# Modular_BO.net
KiCad netlist of a schematic drawn in Altium Designer
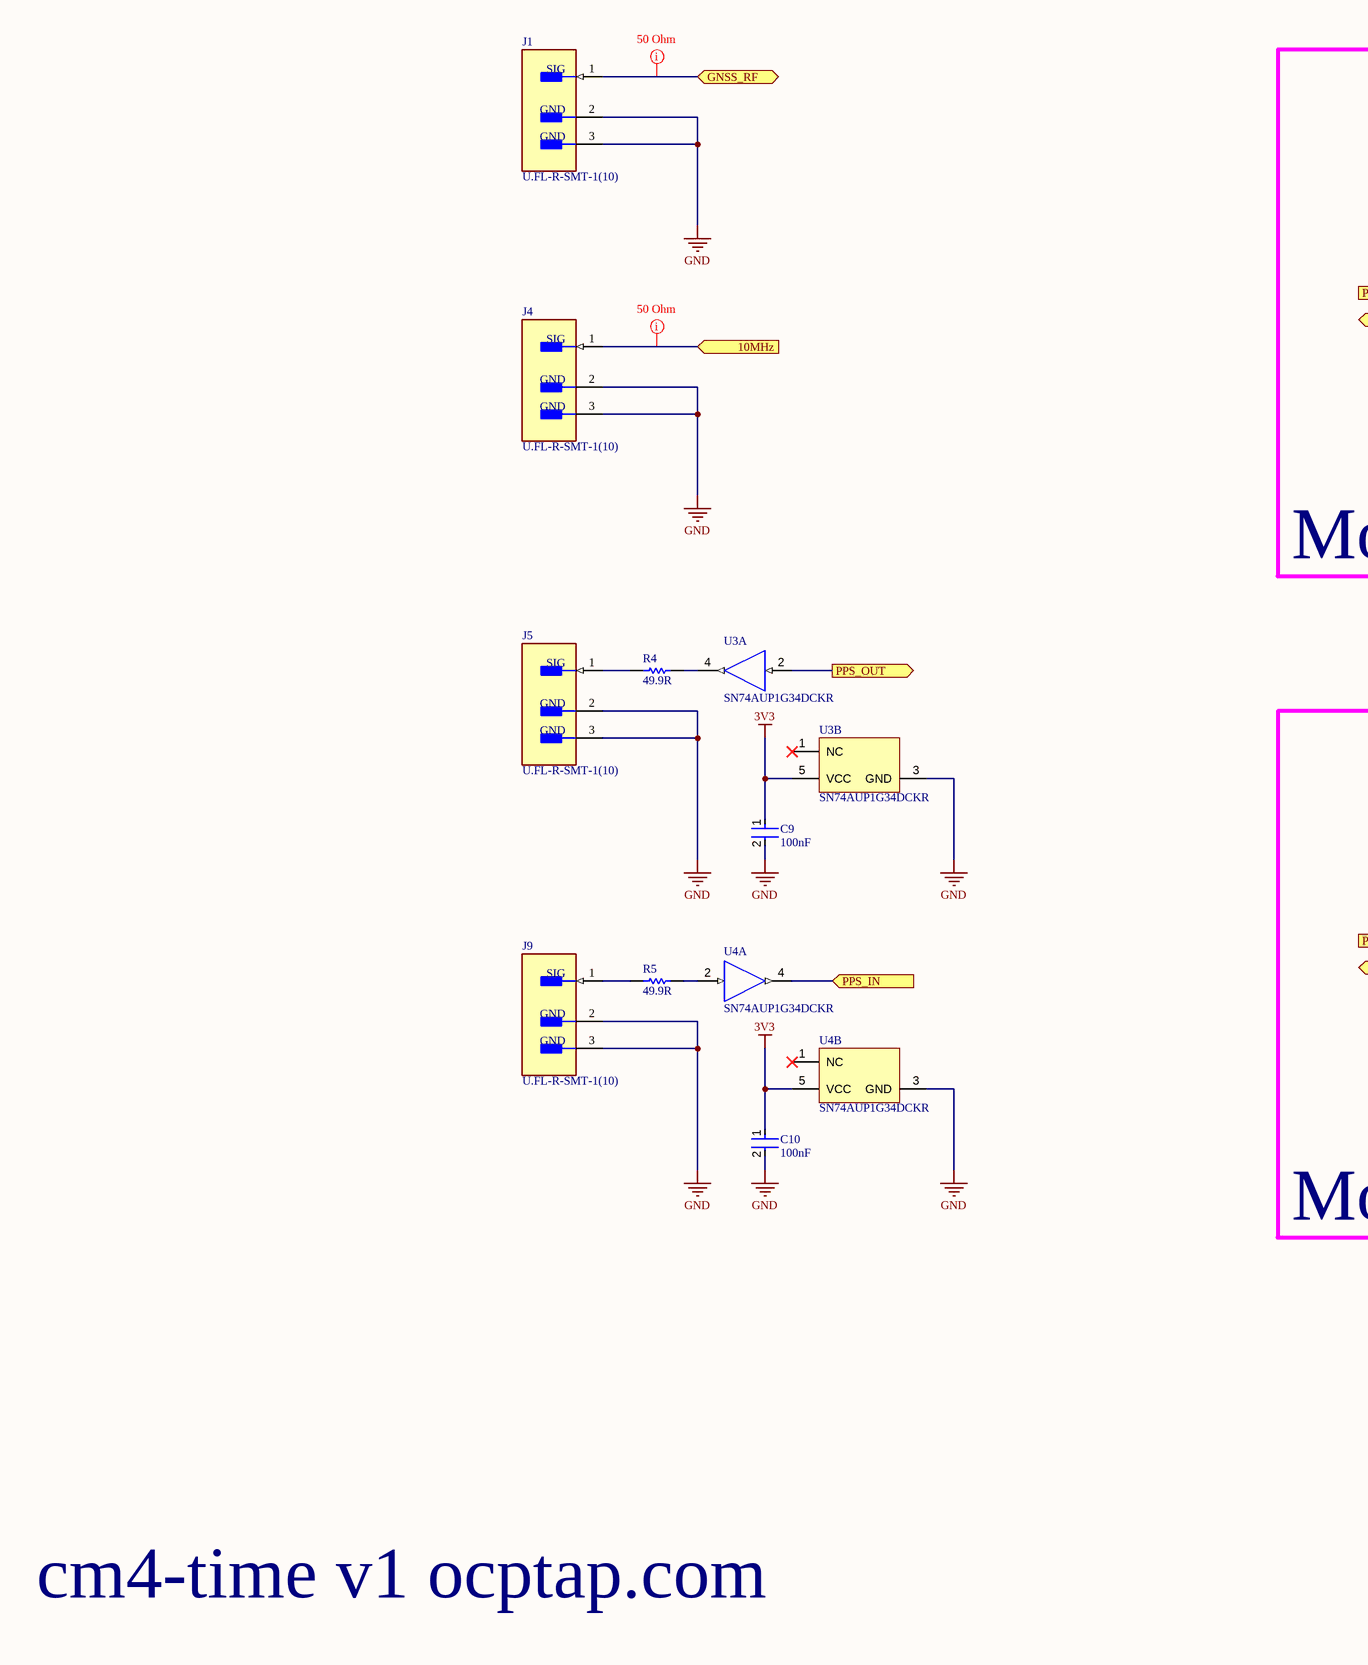
[diagram p0: Modular_BO.SchDoc, left]
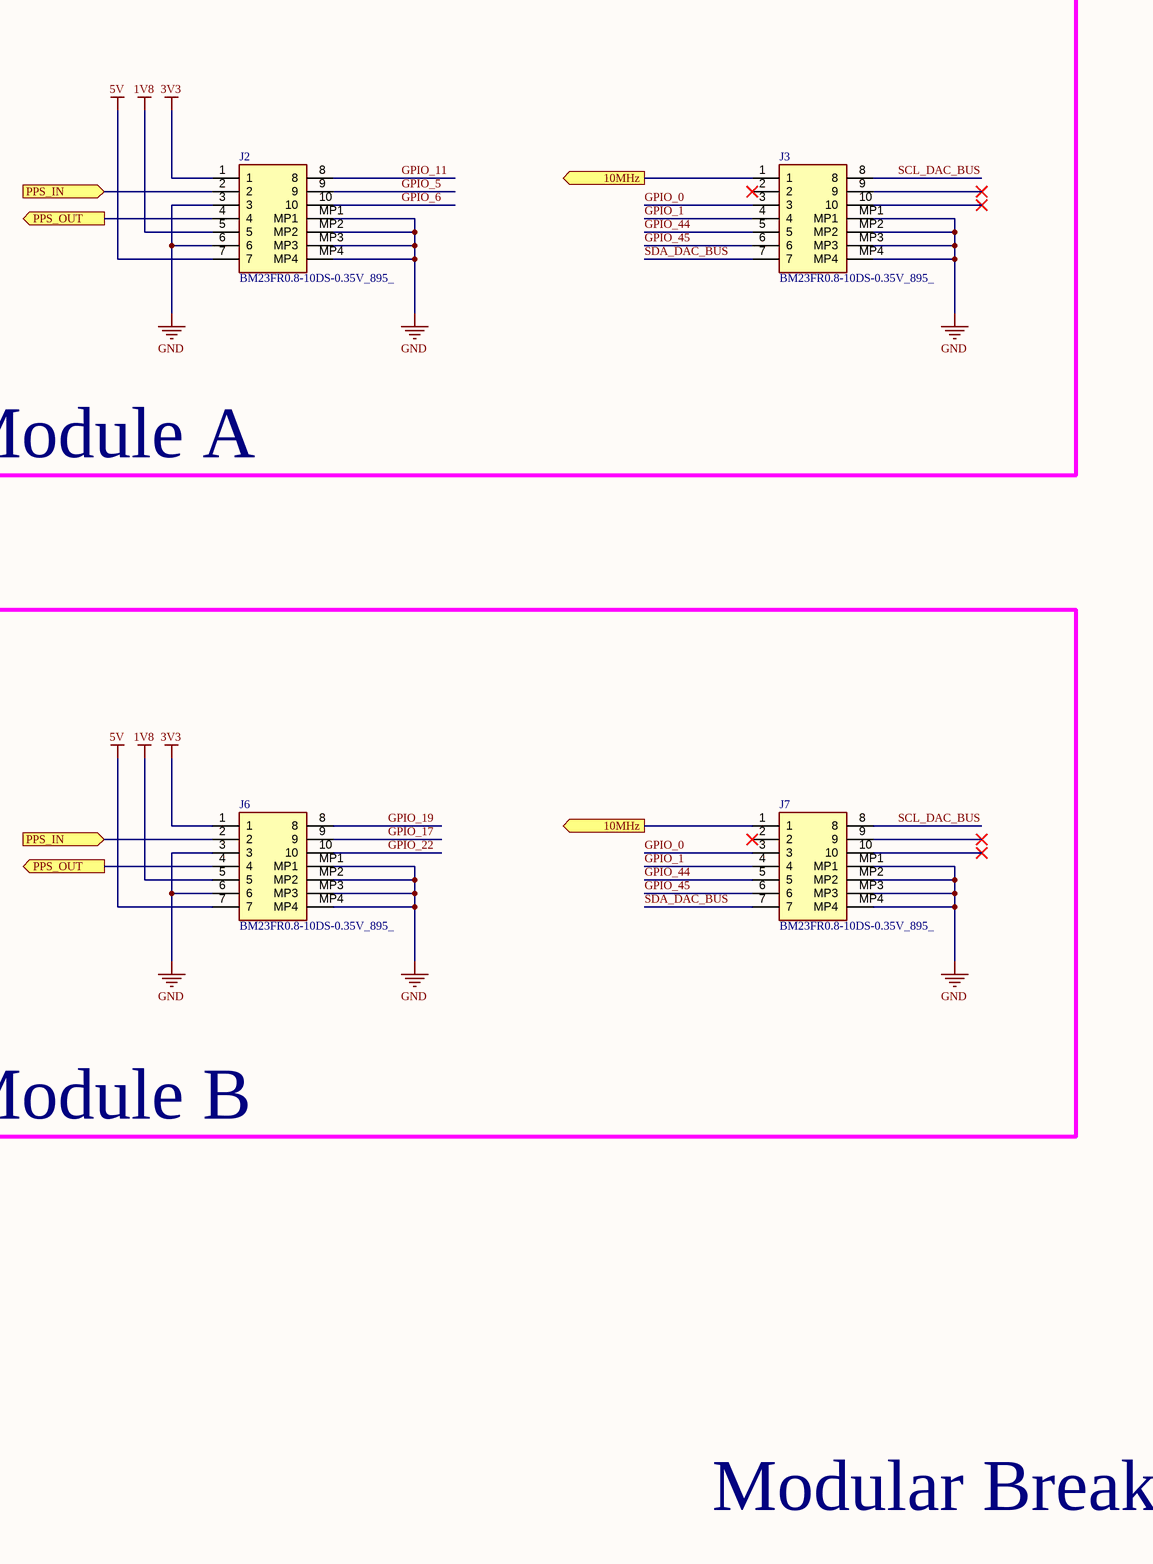
[diagram p1: Modular_BO.SchDoc, right]

(export (version "E")
  (design (tool "Eeschema 10.0.6"))
  (components
    (comp (ref "C9")
      (value "100nF")
      (footprint "FP-C0603C-CF-MFG")
      (description "CAP CER 0.1UF 50V 20% X7R 0603")
      (fields
        (field (name "MANUFACTURER PART NUMBER") "C0603C104M5RACTU")
        (field (name "MANUFACTURER") "KEMET")
      )
      (libsource (lib "Altium Content Vault") (part "b4654b650e69147ec39a6b967a45e02"))
    )
    (comp (ref "C10")
      (value "100nF")
      (footprint "FP-C0603C-CF-MFG")
      (description "CAP CER 0.1UF 50V 20% X7R 0603")
      (fields
        (field (name "MANUFACTURER PART NUMBER") "C0603C104M5RACTU")
        (field (name "MANUFACTURER") "KEMET")
      )
      (libsource (lib "Altium Content Vault") (part "b4654b650e69147ec39a6b967a45e02"))
    )
    (comp (ref "J1")
      (value "U.FL-R-SMT-1(10)")
      (footprint "FP-U_FL-R-SMT-1_10-MFG")
      (description "CONN U.FL RCPT STR 50 OHM SMD")
      (libsource (lib "Altium Content Vault") (part "7158abf7d987fa84906f6fb0d115710"))
    )
    (comp (ref "J2")
      (value "BM23FR0.8-10DS-0.35V_895_")
      (footprint "SamacSys:BM23FR0810DS035V895")
      (description "Connector")
      (fields
        (field (name "MANUFACTURER_PART_NUMBER") "BM23FR0.8-10DS-0.35V(895)")
        (field (name "MOUSER PART NUMBER") "798-3FR0810DS035V895")
      )
      (libsource (lib "*") (part "BM23FR0.8-10DS-0.35V_895_"))
    )
    (comp (ref "J3")
      (value "BM23FR0.8-10DS-0.35V_895_")
      (footprint "SamacSys:BM23FR0810DS035V895")
      (description "Connector")
      (fields
        (field (name "MANUFACTURER_PART_NUMBER") "BM23FR0.8-10DS-0.35V(895)")
        (field (name "MOUSER PART NUMBER") "798-3FR0810DS035V895")
      )
      (libsource (lib "*") (part "BM23FR0.8-10DS-0.35V_895_"))
    )
    (comp (ref "J4")
      (value "U.FL-R-SMT-1(10)")
      (footprint "FP-U_FL-R-SMT-1_10-MFG")
      (description "CONN U.FL RCPT STR 50 OHM SMD")
      (libsource (lib "Altium Content Vault") (part "7158abf7d987fa84906f6fb0d115710"))
    )
    (comp (ref "J5")
      (value "U.FL-R-SMT-1(10)")
      (footprint "FP-U_FL-R-SMT-1_10-MFG")
      (description "CONN U.FL RCPT STR 50 OHM SMD")
      (libsource (lib "Altium Content Vault") (part "7158abf7d987fa84906f6fb0d115710"))
    )
    (comp (ref "J6")
      (value "BM23FR0.8-10DS-0.35V_895_")
      (footprint "SamacSys:BM23FR0810DS035V895")
      (description "Connector")
      (fields
        (field (name "MANUFACTURER_PART_NUMBER") "BM23FR0.8-10DS-0.35V(895)")
        (field (name "MOUSER PART NUMBER") "798-3FR0810DS035V895")
      )
      (libsource (lib "*") (part "BM23FR0.8-10DS-0.35V_895_"))
    )
    (comp (ref "J7")
      (value "BM23FR0.8-10DS-0.35V_895_")
      (footprint "SamacSys:BM23FR0810DS035V895")
      (description "Connector")
      (fields
        (field (name "MANUFACTURER_PART_NUMBER") "BM23FR0.8-10DS-0.35V(895)")
        (field (name "MOUSER PART NUMBER") "798-3FR0810DS035V895")
      )
      (libsource (lib "*") (part "BM23FR0.8-10DS-0.35V_895_"))
    )
    (comp (ref "J9")
      (value "U.FL-R-SMT-1(10)")
      (footprint "FP-U_FL-R-SMT-1_10-MFG")
      (description "CONN U.FL RCPT STR 50 OHM SMD")
      (libsource (lib "Altium Content Vault") (part "7158abf7d987fa84906f6fb0d115710"))
    )
    (comp (ref "R4")
      (value "49.9R")
      (footprint "RESC1608X55X25NL10T15")
      (libsource (lib "Altium Content Vault") (part "RES-2"))
    )
    (comp (ref "R5")
      (value "49.9R")
      (footprint "RESC1608X55X25NL10T15")
      (libsource (lib "Altium Content Vault") (part "RES-2"))
    )
    (comp (ref "U3")
      (value "SN74AUP1G34DCKR")
      (footprint "DCK0005A_M")
      (description "Low-Power Single Buffer Gate, DCK0005A, LARGE T&R")
      (fields
        (field (name "GENERIC PART NUMBER") "SN74AUP1G34")
        (field (name "MANUFACTURER") "Texas Instruments")
      )
      (libsource (lib "") (part "TI-SN74XXX1XXX-XX-5_1"))
    )
    (comp (ref "U4")
      (value "SN74AUP1G34DCKR")
      (footprint "DCK0005A_M")
      (description "Low-Power Single Buffer Gate, DCK0005A, LARGE T&R")
      (fields
        (field (name "GENERIC PART NUMBER") "SN74AUP1G34")
        (field (name "MANUFACTURER") "Texas Instruments")
      )
      (libsource (lib "") (part "TI-SN74XXX1XXX-XX-5_1"))
    )
  )
  (nets
    (net (code "1") (name "/10MHz") (class "Default")
      (node (ref "J3") (pin "1") (pinfunction "1_1") (pintype "passive"))
      (node (ref "J4") (pin "1") (pinfunction "SIG_1") (pintype "input"))
      (node (ref "J7") (pin "1") (pinfunction "1_1") (pintype "passive"))
    )
    (net (code "2") (name "/GNSS_RF") (class "Default")
      (node (ref "J1") (pin "1") (pinfunction "SIG_1") (pintype "input"))
    )
    (net (code "3") (name "/GPIO_0") (class "Default")
      (node (ref "J3") (pin "3") (pinfunction "3_3") (pintype "passive"))
      (node (ref "J7") (pin "3") (pinfunction "3_3") (pintype "passive"))
    )
    (net (code "4") (name "/GPIO_1") (class "Default")
      (node (ref "J3") (pin "4") (pinfunction "4_4") (pintype "passive"))
      (node (ref "J7") (pin "4") (pinfunction "4_4") (pintype "passive"))
    )
    (net (code "5") (name "/GPIO_5") (class "Default")
      (node (ref "J2") (pin "9") (pinfunction "9_9") (pintype "passive"))
    )
    (net (code "6") (name "/GPIO_6") (class "Default")
      (node (ref "J2") (pin "10") (pinfunction "10_10") (pintype "passive"))
    )
    (net (code "7") (name "/GPIO_11") (class "Default")
      (node (ref "J2") (pin "8") (pinfunction "8_8") (pintype "passive"))
    )
    (net (code "8") (name "/GPIO_17") (class "Default")
      (node (ref "J6") (pin "9") (pinfunction "9_9") (pintype "passive"))
    )
    (net (code "9") (name "/GPIO_19") (class "Default")
      (node (ref "J6") (pin "8") (pinfunction "8_8") (pintype "passive"))
    )
    (net (code "10") (name "/GPIO_22") (class "Default")
      (node (ref "J6") (pin "10") (pinfunction "10_10") (pintype "passive"))
    )
    (net (code "11") (name "/GPIO_44") (class "Default")
      (node (ref "J3") (pin "5") (pinfunction "5_5") (pintype "passive"))
      (node (ref "J7") (pin "5") (pinfunction "5_5") (pintype "passive"))
    )
    (net (code "12") (name "/GPIO_45") (class "Default")
      (node (ref "J3") (pin "6") (pinfunction "6_6") (pintype "passive"))
      (node (ref "J7") (pin "6") (pinfunction "6_6") (pintype "passive"))
    )
    (net (code "13") (name "/PPS_IN") (class "Default")
      (node (ref "J2") (pin "2") (pinfunction "2_2") (pintype "passive"))
      (node (ref "J6") (pin "2") (pinfunction "2_2") (pintype "passive"))
      (node (ref "U4") (pin "4") (pinfunction "Y_4") (pintype "output"))
    )
    (net (code "14") (name "/PPS_OUT") (class "Default")
      (node (ref "J2") (pin "4") (pinfunction "4_4") (pintype "passive"))
      (node (ref "J6") (pin "4") (pinfunction "4_4") (pintype "passive"))
      (node (ref "U3") (pin "2") (pinfunction "A_2") (pintype "input"))
    )
    (net (code "15") (name "/SCL_DAC_BUS") (class "Default")
      (node (ref "J3") (pin "8") (pinfunction "8_8") (pintype "passive"))
      (node (ref "J7") (pin "8") (pinfunction "8_8") (pintype "passive"))
    )
    (net (code "16") (name "/SDA_DAC_BUS") (class "Default")
      (node (ref "J3") (pin "7") (pinfunction "7_7") (pintype "passive"))
      (node (ref "J7") (pin "7") (pinfunction "7_7") (pintype "passive"))
    )
    (net (code "17") (name "1V8") (class "Default")
      (node (ref "J2") (pin "5") (pinfunction "5_5") (pintype "passive"))
      (node (ref "J6") (pin "5") (pinfunction "5_5") (pintype "passive"))
    )
    (net (code "18") (name "3V3") (class "Default")
      (node (ref "C10") (pin "1") (pinfunction "1_1") (pintype "passive"))
      (node (ref "C9") (pin "1") (pinfunction "1_1") (pintype "passive"))
      (node (ref "J2") (pin "1") (pinfunction "1_1") (pintype "passive"))
      (node (ref "J6") (pin "1") (pinfunction "1_1") (pintype "passive"))
      (node (ref "U3") (pin "5") (pinfunction "VCC_5") (pintype "power_in"))
      (node (ref "U4") (pin "5") (pinfunction "VCC_5") (pintype "power_in"))
    )
    (net (code "19") (name "5V") (class "Default")
      (node (ref "J2") (pin "7") (pinfunction "7_7") (pintype "passive"))
      (node (ref "J6") (pin "7") (pinfunction "7_7") (pintype "passive"))
    )
    (net (code "20") (name "GND") (class "Default")
      (node (ref "C10") (pin "2") (pinfunction "2_2") (pintype "passive"))
      (node (ref "C9") (pin "2") (pinfunction "2_2") (pintype "passive"))
      (node (ref "J1") (pin "2") (pinfunction "GND_2") (pintype "power_in"))
      (node (ref "J1") (pin "3") (pinfunction "GND_3") (pintype "power_in"))
      (node (ref "J2") (pin "3") (pinfunction "3_3") (pintype "passive"))
      (node (ref "J2") (pin "6") (pinfunction "6_6") (pintype "passive"))
      (node (ref "J2") (pin "MP1") (pinfunction "MP1_MP1") (pintype "passive"))
      (node (ref "J2") (pin "MP2") (pinfunction "MP2_MP2") (pintype "passive"))
      (node (ref "J2") (pin "MP3") (pinfunction "MP3_MP3") (pintype "passive"))
      (node (ref "J2") (pin "MP4") (pinfunction "MP4_MP4") (pintype "passive"))
      (node (ref "J3") (pin "MP1") (pinfunction "MP1_MP1") (pintype "passive"))
      (node (ref "J3") (pin "MP2") (pinfunction "MP2_MP2") (pintype "passive"))
      (node (ref "J3") (pin "MP3") (pinfunction "MP3_MP3") (pintype "passive"))
      (node (ref "J3") (pin "MP4") (pinfunction "MP4_MP4") (pintype "passive"))
      (node (ref "J4") (pin "2") (pinfunction "GND_2") (pintype "power_in"))
      (node (ref "J4") (pin "3") (pinfunction "GND_3") (pintype "power_in"))
      (node (ref "J5") (pin "2") (pinfunction "GND_2") (pintype "power_in"))
      (node (ref "J5") (pin "3") (pinfunction "GND_3") (pintype "power_in"))
      (node (ref "J6") (pin "3") (pinfunction "3_3") (pintype "passive"))
      (node (ref "J6") (pin "6") (pinfunction "6_6") (pintype "passive"))
      (node (ref "J6") (pin "MP1") (pinfunction "MP1_MP1") (pintype "passive"))
      (node (ref "J6") (pin "MP2") (pinfunction "MP2_MP2") (pintype "passive"))
      (node (ref "J6") (pin "MP3") (pinfunction "MP3_MP3") (pintype "passive"))
      (node (ref "J6") (pin "MP4") (pinfunction "MP4_MP4") (pintype "passive"))
      (node (ref "J7") (pin "MP1") (pinfunction "MP1_MP1") (pintype "passive"))
      (node (ref "J7") (pin "MP2") (pinfunction "MP2_MP2") (pintype "passive"))
      (node (ref "J7") (pin "MP3") (pinfunction "MP3_MP3") (pintype "passive"))
      (node (ref "J7") (pin "MP4") (pinfunction "MP4_MP4") (pintype "passive"))
      (node (ref "J9") (pin "2") (pinfunction "GND_2") (pintype "power_in"))
      (node (ref "J9") (pin "3") (pinfunction "GND_3") (pintype "power_in"))
      (node (ref "U3") (pin "3") (pinfunction "GND_3") (pintype "power_in"))
      (node (ref "U4") (pin "3") (pinfunction "GND_3") (pintype "power_in"))
    )
    (net (code "21") (name "Net-(J5-SIG)") (class "Default")
      (node (ref "J5") (pin "1") (pinfunction "SIG_1") (pintype "input"))
      (node (ref "R4") (pin "1") (pinfunction "1_1") (pintype "passive"))
    )
    (net (code "22") (name "Net-(J9-SIG)") (class "Default")
      (node (ref "J9") (pin "1") (pinfunction "SIG_1") (pintype "input"))
      (node (ref "R5") (pin "1") (pinfunction "1_1") (pintype "passive"))
    )
    (net (code "23") (name "Net-(U3A-Y)") (class "Default")
      (node (ref "R4") (pin "2") (pinfunction "2_2") (pintype "passive"))
      (node (ref "U3") (pin "4") (pinfunction "Y_4") (pintype "output"))
    )
    (net (code "24") (name "Net-(U4A-A)") (class "Default")
      (node (ref "R5") (pin "2") (pinfunction "2_2") (pintype "passive"))
      (node (ref "U4") (pin "2") (pinfunction "A_2") (pintype "input"))
    )
    (net (code "25") (name "unconnected-(J3-Pad2)") (class "Default")
      (node (ref "J3") (pin "2") (pinfunction "2_2") (pintype "passive+no_connect"))
    )
    (net (code "26") (name "unconnected-(J3-Pad9)") (class "Default")
      (node (ref "J3") (pin "9") (pinfunction "9_9") (pintype "passive+no_connect"))
    )
    (net (code "27") (name "unconnected-(J3-Pad10)") (class "Default")
      (node (ref "J3") (pin "10") (pinfunction "10_10") (pintype "passive+no_connect"))
    )
    (net (code "28") (name "unconnected-(J7-Pad2)") (class "Default")
      (node (ref "J7") (pin "2") (pinfunction "2_2") (pintype "passive+no_connect"))
    )
    (net (code "29") (name "unconnected-(J7-Pad9)") (class "Default")
      (node (ref "J7") (pin "9") (pinfunction "9_9") (pintype "passive+no_connect"))
    )
    (net (code "30") (name "unconnected-(J7-Pad10)") (class "Default")
      (node (ref "J7") (pin "10") (pinfunction "10_10") (pintype "passive+no_connect"))
    )
    (net (code "31") (name "unconnected-(U3B-NC-Pad1)") (class "Default")
      (node (ref "U3") (pin "1") (pinfunction "NC_1") (pintype "passive+no_connect"))
    )
    (net (code "32") (name "unconnected-(U4B-NC-Pad1)") (class "Default")
      (node (ref "U4") (pin "1") (pinfunction "NC_1") (pintype "passive+no_connect"))
    )
  )
)
